# CPU.net
KiCad netlist of a schematic drawn in Altium Designer
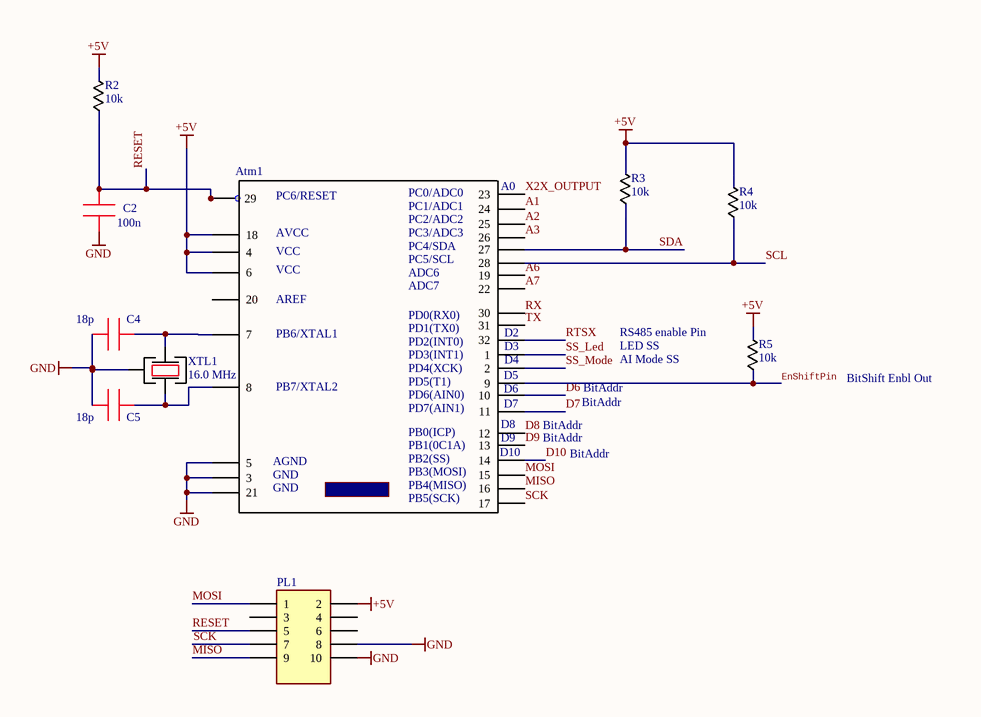
[diagram p0: CPU.SchDoc]

(export (version "E")
  (design (tool "Eeschema 10.0.6"))
  (components
    (comp (ref "Atm1")
      (value "~")
      (footprint "TQFP")
      (fields (field (name "PART NUMBER") "Atmega328P-AU"))
      (libsource (lib "kontr") (part "Atmega328"))
    )
    (comp (ref "C2")
      (value "100n")
      (footprint "0603 - Cap")
      (description "CC0603ZRY5V9BB104")
      (fields (field (name "PART NUMBER") "CC0603KRX7R9BB104"))
      (libsource (lib "kontr") (part "Capasitor 0805"))
    )
    (comp (ref "C4")
      (value "18p")
      (footprint "0603 - Cap")
      (fields (field (name "PART NUMBER") "CC0603JRNPO9BN180"))
      (libsource (lib "kontr") (part "Capasitor 0805"))
    )
    (comp (ref "C5")
      (value "18p")
      (footprint "0603 - Cap")
      (fields (field (name "PART NUMBER") "CC0603JRNPO9BN180"))
      (libsource (lib "kontr") (part "Capasitor 0805"))
    )
    (comp (ref "PL1")
      (value "~")
      (footprint "IDC-10MS")
      (fields (field (name "PART NUMBER") "DS1013-10SSIB1-B-0"))
      (libsource (lib "kontr") (part "IDC-10MS"))
    )
    (comp (ref "R2")
      (value "10k")
      (footprint "0603_Res")
      (description "RT0603FRE0710KL")
      (fields (field (name "PART NUMBER") "RC0603FR-0710KL"))
      (libsource (lib "kontr") (part "Resistor 0805"))
    )
    (comp (ref "R3")
      (value "10k")
      (footprint "0603_Res")
      (description "RC0402FR-0710KL")
      (fields (field (name "PART NUMBER") "RC0603FR-0710KL"))
      (libsource (lib "kontr") (part "Resistor 0805"))
    )
    (comp (ref "R4")
      (value "10k")
      (footprint "0603_Res")
      (description "RC0402FR-0710KL")
      (fields (field (name "PART NUMBER") "RC0603FR-0710KL"))
      (libsource (lib "kontr") (part "Resistor 0805"))
    )
    (comp (ref "R5")
      (value "10k")
      (footprint "0603_Res")
      (description "RC0402FR-0710KL")
      (fields (field (name "PART NUMBER") "RC0603FR-0710KL"))
      (libsource (lib "kontr") (part "Resistor 0805"))
    )
    (comp (ref "XTL1")
      (value "16.0 MHz")
      (footprint "KX-7 XTAL")
      (fields (field (name "PART NUMBER") "Geyer KX-7 16.0 MHz"))
      (libsource (lib "kontr") (part "KX-7"))
    )
  )
  (nets
    (net (code "1") (name "+5V") (class "Default")
      (node (ref "Atm1") (pin "18") (pinfunction "18_18") (pintype "passive"))
      (node (ref "Atm1") (pin "4") (pinfunction "4_4") (pintype "passive"))
      (node (ref "Atm1") (pin "6") (pinfunction "6_6") (pintype "passive"))
      (node (ref "PL1") (pin "2") (pinfunction "2_2") (pintype "passive"))
      (node (ref "R2") (pin "2") (pintype "passive"))
      (node (ref "R3") (pin "2") (pintype "passive"))
      (node (ref "R4") (pin "2") (pintype "passive"))
      (node (ref "R5") (pin "2") (pintype "passive"))
    )
    (net (code "2") (name "/A1") (class "Default")
      (node (ref "Atm1") (pin "24") (pinfunction "24_24") (pintype "passive"))
    )
    (net (code "3") (name "/A2") (class "Default")
      (node (ref "Atm1") (pin "25") (pinfunction "25_25") (pintype "passive"))
    )
    (net (code "4") (name "/A3") (class "Default")
      (node (ref "Atm1") (pin "26") (pinfunction "26_26") (pintype "passive"))
    )
    (net (code "5") (name "/A6") (class "Default")
      (node (ref "Atm1") (pin "19") (pinfunction "19_19") (pintype "passive"))
    )
    (net (code "6") (name "/A7") (class "Default")
      (node (ref "Atm1") (pin "22") (pinfunction "22_22") (pintype "passive"))
    )
    (net (code "7") (name "/D6") (class "Default")
      (node (ref "Atm1") (pin "10") (pinfunction "10_10") (pintype "passive"))
    )
    (net (code "8") (name "/D7") (class "Default")
      (node (ref "Atm1") (pin "11") (pinfunction "11_11") (pintype "passive"))
    )
    (net (code "9") (name "/D8") (class "Default")
      (node (ref "Atm1") (pin "12") (pinfunction "12_12") (pintype "passive"))
    )
    (net (code "10") (name "/D9") (class "Default")
      (node (ref "Atm1") (pin "13") (pinfunction "13_13") (pintype "passive"))
    )
    (net (code "11") (name "/D10") (class "Default")
      (node (ref "Atm1") (pin "14") (pinfunction "14_14") (pintype "passive"))
    )
    (net (code "12") (name "/EnShiftPin") (class "Default")
      (node (ref "Atm1") (pin "9") (pinfunction "9_9") (pintype "passive"))
      (node (ref "R5") (pin "1") (pintype "passive"))
    )
    (net (code "13") (name "/MISO") (class "Default")
      (node (ref "Atm1") (pin "16") (pinfunction "16_16") (pintype "passive"))
      (node (ref "PL1") (pin "9") (pinfunction "9_9") (pintype "passive"))
    )
    (net (code "14") (name "/MOSI") (class "Default")
      (node (ref "Atm1") (pin "15") (pinfunction "15_15") (pintype "passive"))
      (node (ref "PL1") (pin "1") (pinfunction "1_1") (pintype "passive"))
    )
    (net (code "15") (name "/RESET") (class "Default")
      (node (ref "Atm1") (pin "29") (pinfunction "29_29") (pintype "passive"))
      (node (ref "C2") (pin "2") (pinfunction "2_2") (pintype "passive"))
      (node (ref "PL1") (pin "5") (pinfunction "5_5") (pintype "passive"))
      (node (ref "R2") (pin "1") (pintype "passive"))
    )
    (net (code "16") (name "/RTSX") (class "Default")
      (node (ref "Atm1") (pin "32") (pinfunction "32_32") (pintype "passive"))
    )
    (net (code "17") (name "/RX") (class "Default")
      (node (ref "Atm1") (pin "30") (pinfunction "30_30") (pintype "passive"))
    )
    (net (code "18") (name "/SCK") (class "Default")
      (node (ref "Atm1") (pin "17") (pinfunction "17_17") (pintype "passive"))
      (node (ref "PL1") (pin "7") (pinfunction "7_7") (pintype "passive"))
    )
    (net (code "19") (name "/SCL") (class "Default")
      (node (ref "Atm1") (pin "28") (pinfunction "28_28") (pintype "passive"))
      (node (ref "R4") (pin "1") (pintype "passive"))
    )
    (net (code "20") (name "/SDA") (class "Default")
      (node (ref "Atm1") (pin "27") (pinfunction "27_27") (pintype "passive"))
      (node (ref "R3") (pin "1") (pintype "passive"))
    )
    (net (code "21") (name "/SS_Led") (class "Default")
      (node (ref "Atm1") (pin "1") (pinfunction "1_1") (pintype "passive"))
    )
    (net (code "22") (name "/SS_Mode") (class "Default")
      (node (ref "Atm1") (pin "2") (pinfunction "2_2") (pintype "passive"))
    )
    (net (code "23") (name "/TX") (class "Default")
      (node (ref "Atm1") (pin "31") (pinfunction "31_31") (pintype "passive"))
    )
    (net (code "24") (name "/X2X_OUTPUT") (class "Default")
      (node (ref "Atm1") (pin "23") (pinfunction "23_23") (pintype "passive"))
    )
    (net (code "25") (name "GND") (class "Default")
      (node (ref "Atm1") (pin "21") (pinfunction "21_21") (pintype "passive"))
      (node (ref "Atm1") (pin "3") (pinfunction "3_3") (pintype "passive"))
      (node (ref "Atm1") (pin "5") (pinfunction "5_5") (pintype "passive"))
      (node (ref "C2") (pin "1") (pinfunction "1_1") (pintype "passive"))
      (node (ref "C4") (pin "1") (pinfunction "1_1") (pintype "passive"))
      (node (ref "C5") (pin "1") (pinfunction "1_1") (pintype "passive"))
      (node (ref "PL1") (pin "10") (pinfunction "10_10") (pintype "passive"))
      (node (ref "PL1") (pin "8") (pinfunction "8_8") (pintype "passive"))
      (node (ref "XTL1") (pin "2") (pinfunction "2_2") (pintype "passive"))
    )
    (net (code "26") (name "Net-(Atm1-Pad7)") (class "Default")
      (node (ref "Atm1") (pin "7") (pinfunction "7_7") (pintype "passive"))
      (node (ref "C4") (pin "2") (pinfunction "2_2") (pintype "passive"))
      (node (ref "XTL1") (pin "1") (pinfunction "5_1") (pintype "passive"))
    )
    (net (code "27") (name "Net-(Atm1-Pad8)") (class "Default")
      (node (ref "Atm1") (pin "8") (pinfunction "8_8") (pintype "passive"))
      (node (ref "C5") (pin "2") (pinfunction "2_2") (pintype "passive"))
      (node (ref "XTL1") (pin "3") (pinfunction "5_3") (pintype "passive"))
    )
    (net (code "28") (name "unconnected-(Atm1-Pad20)") (class "Default")
      (node (ref "Atm1") (pin "20") (pinfunction "20_20") (pintype "passive"))
    )
    (net (code "29") (name "unconnected-(PL1-Pad3)") (class "Default")
      (node (ref "PL1") (pin "3") (pinfunction "3_3") (pintype "passive"))
    )
    (net (code "30") (name "unconnected-(PL1-Pad4)") (class "Default")
      (node (ref "PL1") (pin "4") (pinfunction "4_4") (pintype "passive"))
    )
    (net (code "31") (name "unconnected-(PL1-Pad6)") (class "Default")
      (node (ref "PL1") (pin "6") (pinfunction "6_6") (pintype "passive"))
    )
  )
)
